# weller.net
KiCad netlist of a schematic drawn in Altium Designer
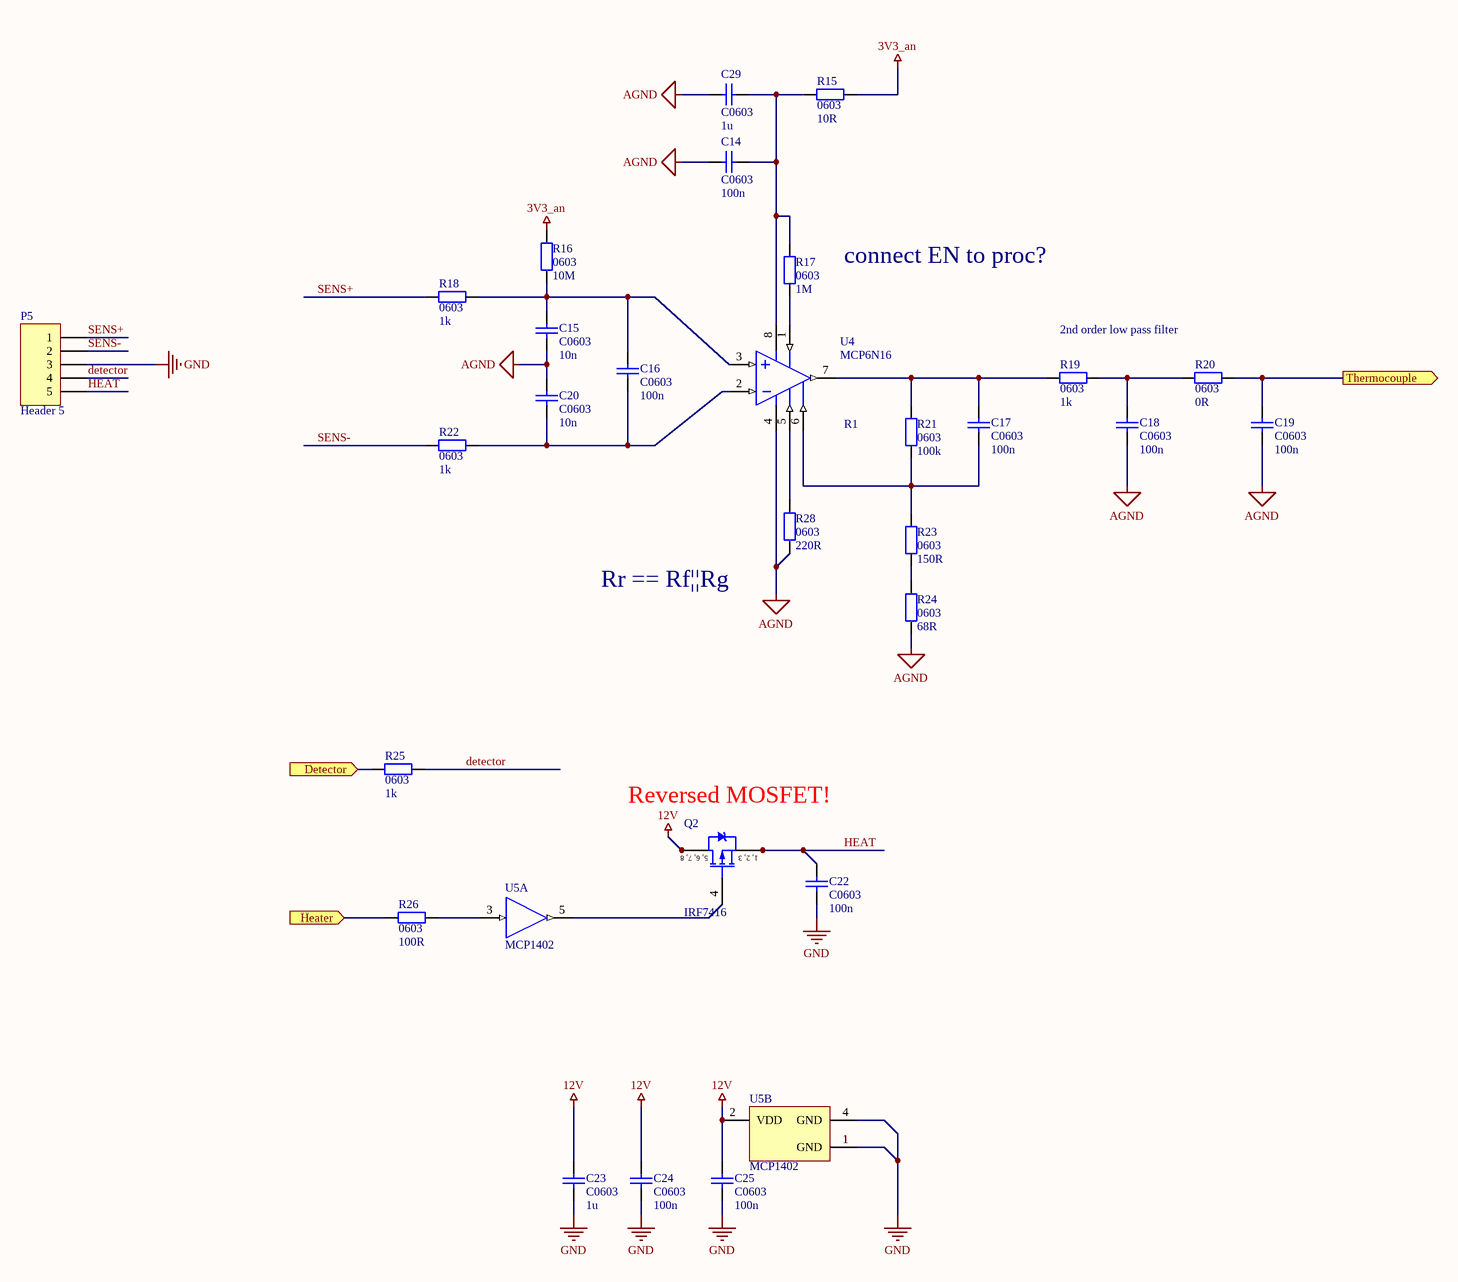
[diagram p0: weller.SchDoc]

(export (version "E")
  (design (tool "Eeschema 10.0.6"))
  (components
    (comp (ref "C14")
      (value "100n")
      (footprint "C0603")
      (description "Generic capacitor")
      (libsource (lib "_RLC") (part "Cap"))
    )
    (comp (ref "C15")
      (value "10n")
      (footprint "C0603")
      (description "Generic capacitor")
      (libsource (lib "_RLC") (part "Cap"))
    )
    (comp (ref "C16")
      (value "100n")
      (footprint "C0603")
      (description "Generic capacitor")
      (libsource (lib "_RLC") (part "Cap"))
    )
    (comp (ref "C17")
      (value "100n")
      (footprint "C0603")
      (description "Generic capacitor")
      (libsource (lib "_RLC") (part "Cap"))
    )
    (comp (ref "C18")
      (value "100n")
      (footprint "C0603")
      (description "Generic capacitor")
      (libsource (lib "_RLC") (part "Cap"))
    )
    (comp (ref "C19")
      (value "100n")
      (footprint "C0603")
      (description "Generic capacitor")
      (libsource (lib "_RLC") (part "Cap"))
    )
    (comp (ref "C20")
      (value "10n")
      (footprint "C0603")
      (description "Generic capacitor")
      (libsource (lib "_RLC") (part "Cap"))
    )
    (comp (ref "C22")
      (value "100n")
      (footprint "C0603")
      (description "Generic capacitor")
      (libsource (lib "_RLC") (part "Cap"))
    )
    (comp (ref "C23")
      (value "1u")
      (footprint "C0603")
      (description "Generic capacitor")
      (libsource (lib "_RLC") (part "Cap"))
    )
    (comp (ref "C24")
      (value "100n")
      (footprint "C0603")
      (description "Generic capacitor")
      (libsource (lib "_RLC") (part "Cap"))
    )
    (comp (ref "C25")
      (value "100n")
      (footprint "C0603")
      (description "Generic capacitor")
      (libsource (lib "_RLC") (part "Cap"))
    )
    (comp (ref "C29")
      (value "1u")
      (footprint "C0603")
      (description "Generic capacitor")
      (libsource (lib "_RLC") (part "Cap"))
    )
    (comp (ref "P5")
      (value "Header 5")
      (footprint "HDR1X5")
      (description "Header, 5-Pin")
      (fields (field (name "PUBLISHER") "Altium Limited"))
      (libsource (lib "_Connectors") (part "Header 5"))
    )
    (comp (ref "Q2")
      (value "IRF7416")
      (footprint "SOIC-8_M")
      (description "Power P-MOSFET")
      (fields (field (name "PUBLISHER") "Altium Limited"))
      (libsource (lib "_Transistors") (part "IRF7416"))
    )
    (comp (ref "R15")
      (value "10R")
      (footprint "0603")
      (description "Generic resistor")
      (libsource (lib "") (part "Res_2"))
    )
    (comp (ref "R16")
      (value "10M")
      (footprint "0603")
      (description "Generic resistor")
      (libsource (lib "_RLC") (part "Res"))
    )
    (comp (ref "R17")
      (value "1M")
      (footprint "0603")
      (description "Generic resistor")
      (libsource (lib "_RLC") (part "Res"))
    )
    (comp (ref "R18")
      (value "1k")
      (footprint "0603")
      (description "Generic resistor")
      (libsource (lib "") (part "Res_1"))
    )
    (comp (ref "R19")
      (value "1k")
      (footprint "0603")
      (description "Generic resistor")
      (libsource (lib "") (part "Res_1"))
    )
    (comp (ref "R20")
      (value "0R")
      (footprint "0603")
      (description "Generic resistor")
      (libsource (lib "") (part "Res_1"))
    )
    (comp (ref "R21")
      (value "100k")
      (footprint "0603")
      (description "Generic resistor")
      (libsource (lib "_RLC") (part "Res"))
    )
    (comp (ref "R22")
      (value "1k")
      (footprint "0603")
      (description "Generic resistor")
      (libsource (lib "") (part "Res_1"))
    )
    (comp (ref "R23")
      (value "150R")
      (footprint "0603")
      (description "Generic resistor")
      (libsource (lib "_RLC") (part "Res"))
    )
    (comp (ref "R24")
      (value "68R")
      (footprint "0603")
      (description "Generic resistor")
      (libsource (lib "_RLC") (part "Res"))
    )
    (comp (ref "R25")
      (value "1k")
      (footprint "0603")
      (description "Generic resistor")
      (libsource (lib "") (part "Res_1"))
    )
    (comp (ref "R26")
      (value "100R")
      (footprint "0603")
      (description "Generic resistor")
      (libsource (lib "") (part "Res_1"))
    )
    (comp (ref "R28")
      (value "220R")
      (footprint "0603")
      (description "Generic resistor")
      (libsource (lib "_RLC") (part "Res"))
    )
    (comp (ref "U4")
      (value "MCP6N16")
      (footprint "MSOP-MS8_M")
      (libsource (lib "_Microcircuits") (part "MCP6N16"))
    )
    (comp (ref "U5")
      (value "MCP1402")
      (footprint "SOT23-5_M")
      (description "MCP1402 MOSFET driver")
      (libsource (lib "_Microcircuits") (part "MCP1402"))
    )
  )
  (nets
    (net (code "1") (name "/Detector") (class "Default")
      (node (ref "R25") (pin "1") (pinfunction "1_1") (pintype "passive"))
    )
    (net (code "2") (name "/HEAT") (class "Default")
      (node (ref "C22") (pin "1") (pinfunction "1_1") (pintype "passive"))
      (node (ref "P5") (pin "5") (pinfunction "5_5") (pintype "passive"))
      (node (ref "Q2") (pin "1") (pinfunction "S_1") (pintype "passive"))
      (node (ref "Q2") (pin "2") (pinfunction "S_2") (pintype "passive"))
      (node (ref "Q2") (pin "3") (pinfunction "S_3") (pintype "passive"))
    )
    (net (code "3") (name "/Heater") (class "Default")
      (node (ref "R26") (pin "1") (pinfunction "1_1") (pintype "passive"))
    )
    (net (code "4") (name "/SENS+") (class "Default")
      (node (ref "P5") (pin "1") (pinfunction "1_1") (pintype "passive"))
      (node (ref "R18") (pin "1") (pinfunction "1_1") (pintype "passive"))
    )
    (net (code "5") (name "/SENS-") (class "Default")
      (node (ref "P5") (pin "2") (pinfunction "2_2") (pintype "passive"))
      (node (ref "R22") (pin "1") (pinfunction "1_1") (pintype "passive"))
    )
    (net (code "6") (name "/Thermocouple") (class "Default")
      (node (ref "C19") (pin "1") (pinfunction "1_1") (pintype "passive"))
      (node (ref "R20") (pin "2") (pinfunction "2_2") (pintype "passive"))
    )
    (net (code "7") (name "/detector") (class "Default")
      (node (ref "P5") (pin "4") (pinfunction "4_4") (pintype "passive"))
      (node (ref "R25") (pin "2") (pinfunction "2_2") (pintype "passive"))
    )
    (net (code "8") (name "3V3_an") (class "Default")
      (node (ref "R15") (pin "1") (pinfunction "1_1") (pintype "passive"))
      (node (ref "R16") (pin "1") (pinfunction "1_1") (pintype "passive"))
    )
    (net (code "9") (name "12V") (class "Default")
      (node (ref "C23") (pin "1") (pinfunction "1_1") (pintype "passive"))
      (node (ref "C24") (pin "1") (pinfunction "1_1") (pintype "passive"))
      (node (ref "C25") (pin "1") (pinfunction "1_1") (pintype "passive"))
      (node (ref "Q2") (pin "5") (pinfunction "D_5") (pintype "passive"))
      (node (ref "Q2") (pin "6") (pinfunction "D_6") (pintype "passive"))
      (node (ref "Q2") (pin "7") (pinfunction "D_7") (pintype "passive"))
      (node (ref "Q2") (pin "8") (pinfunction "D_8") (pintype "passive"))
      (node (ref "U5") (pin "2") (pinfunction "VDD_2") (pintype "power_in"))
    )
    (net (code "10") (name "AGND") (class "Default")
      (node (ref "C14") (pin "1") (pinfunction "1_1") (pintype "passive"))
      (node (ref "C15") (pin "1") (pinfunction "1_1") (pintype "passive"))
      (node (ref "C18") (pin "2") (pinfunction "2_2") (pintype "passive"))
      (node (ref "C19") (pin "2") (pinfunction "2_2") (pintype "passive"))
      (node (ref "C20") (pin "1") (pinfunction "1_1") (pintype "passive"))
      (node (ref "C29") (pin "2") (pinfunction "2_2") (pintype "passive"))
      (node (ref "R24") (pin "2") (pinfunction "2_2") (pintype "passive"))
      (node (ref "R28") (pin "2") (pinfunction "2_2") (pintype "passive"))
      (node (ref "U4") (pin "4") (pinfunction "VSS_4") (pintype "power_in"))
    )
    (net (code "11") (name "GND") (class "Default")
      (node (ref "C22") (pin "2") (pinfunction "2_2") (pintype "passive"))
      (node (ref "C23") (pin "2") (pinfunction "2_2") (pintype "passive"))
      (node (ref "C24") (pin "2") (pinfunction "2_2") (pintype "passive"))
      (node (ref "C25") (pin "2") (pinfunction "2_2") (pintype "passive"))
      (node (ref "P5") (pin "3") (pinfunction "3_3") (pintype "passive"))
      (node (ref "U5") (pin "1") (pinfunction "GND_1") (pintype "power_in"))
      (node (ref "U5") (pin "4") (pinfunction "GND_4") (pintype "power_in"))
    )
    (net (code "12") (name "Net-(C18-Pad1)") (class "Default")
      (node (ref "C18") (pin "1") (pinfunction "1_1") (pintype "passive"))
      (node (ref "R19") (pin "2") (pinfunction "2_2") (pintype "passive"))
      (node (ref "R20") (pin "1") (pinfunction "1_1") (pintype "passive"))
    )
    (net (code "13") (name "Net-(Q2-G)") (class "Default")
      (node (ref "Q2") (pin "4") (pinfunction "G_4") (pintype "passive"))
      (node (ref "U5") (pin "5") (pinfunction "OUT_5") (pintype "output"))
    )
    (net (code "14") (name "Net-(R23-Pad2)") (class "Default")
      (node (ref "R23") (pin "2") (pinfunction "2_2") (pintype "passive"))
      (node (ref "R24") (pin "1") (pinfunction "1_1") (pintype "passive"))
    )
    (net (code "15") (name "Net-(U4-EN)") (class "Default")
      (node (ref "R17") (pin "2") (pinfunction "2_2") (pintype "passive"))
      (node (ref "U4") (pin "1") (pinfunction "EN_1") (pintype "input"))
    )
    (net (code "16") (name "Net-(U4-FB)") (class "Default")
      (node (ref "C17") (pin "2") (pinfunction "2_2") (pintype "passive"))
      (node (ref "R21") (pin "2") (pinfunction "2_2") (pintype "passive"))
      (node (ref "R23") (pin "1") (pinfunction "1_1") (pintype "passive"))
      (node (ref "U4") (pin "6") (pinfunction "FB_6") (pintype "input"))
    )
    (net (code "17") (name "Net-(U4-VDD)") (class "Default")
      (node (ref "C14") (pin "2") (pinfunction "2_2") (pintype "passive"))
      (node (ref "C29") (pin "1") (pinfunction "1_1") (pintype "passive"))
      (node (ref "R15") (pin "2") (pinfunction "2_2") (pintype "passive"))
      (node (ref "R17") (pin "1") (pinfunction "1_1") (pintype "passive"))
      (node (ref "U4") (pin "8") (pinfunction "VDD_8") (pintype "power_in"))
    )
    (net (code "18") (name "Net-(U4-VIN+)") (class "Default")
      (node (ref "C15") (pin "2") (pinfunction "2_2") (pintype "passive"))
      (node (ref "C16") (pin "1") (pinfunction "1_1") (pintype "passive"))
      (node (ref "R16") (pin "2") (pinfunction "2_2") (pintype "passive"))
      (node (ref "R18") (pin "2") (pinfunction "2_2") (pintype "passive"))
      (node (ref "U4") (pin "3") (pinfunction "VIN+_3") (pintype "input"))
    )
    (net (code "19") (name "Net-(U4-VIN-)") (class "Default")
      (node (ref "C16") (pin "2") (pinfunction "2_2") (pintype "passive"))
      (node (ref "C20") (pin "2") (pinfunction "2_2") (pintype "passive"))
      (node (ref "R22") (pin "2") (pinfunction "2_2") (pintype "passive"))
      (node (ref "U4") (pin "2") (pinfunction "VIN-_2") (pintype "input"))
    )
    (net (code "20") (name "Net-(U4-VOUT)") (class "Default")
      (node (ref "C17") (pin "1") (pinfunction "1_1") (pintype "passive"))
      (node (ref "R19") (pin "1") (pinfunction "1_1") (pintype "passive"))
      (node (ref "R21") (pin "1") (pinfunction "1_1") (pintype "passive"))
      (node (ref "U4") (pin "7") (pinfunction "VOUT_7") (pintype "output"))
    )
    (net (code "21") (name "Net-(U4-Vref)") (class "Default")
      (node (ref "R28") (pin "1") (pinfunction "1_1") (pintype "passive"))
      (node (ref "U4") (pin "5") (pinfunction "Vref_5") (pintype "input"))
    )
    (net (code "22") (name "Net-(U5A-IN)") (class "Default")
      (node (ref "R26") (pin "2") (pinfunction "2_2") (pintype "passive"))
      (node (ref "U5") (pin "3") (pinfunction "IN_3") (pintype "input"))
    )
  )
)
